# WarpCoreControl.net
KiCad netlist of a schematic drawn in EAGLE
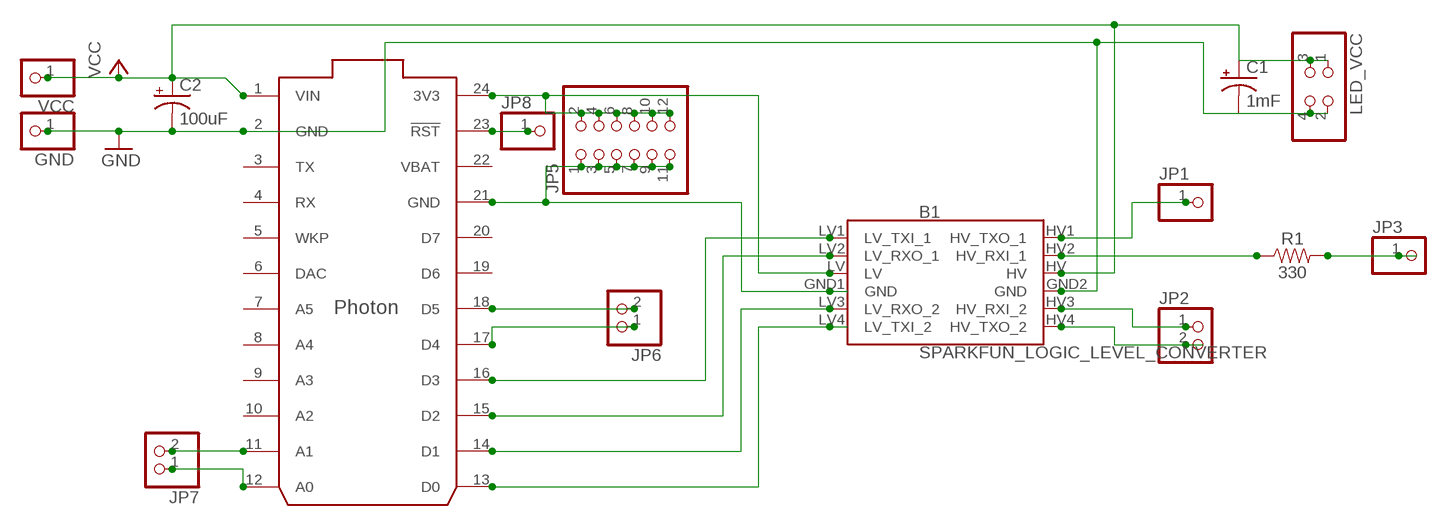
[diagram p0: schematic, sheet 1]

(export (version "E")
  (design (tool "Eeschema 10.0.6"))
  (components
    (comp (ref "B1")
      (value "SPARKFUN_LOGIC_LEVEL_CONVERTER")
      (footprint "eagle-import:SPARKFUN_LOGIC_LEVEL_CONVERTER")
      (libsource (lib "eagle-import") (part "SPARKFUN_LOGIC_LEVEL_CONVERTER"))
    )
    (comp (ref "C1")
      (value "1mF")
      (footprint "eagle-import:CPOL-RADIAL-5MM-10MM")
      (libsource (lib "eagle-import") (part "1000UF-RADIAL-5MM-25V-20%"))
    )
    (comp (ref "C2")
      (value "100uF")
      (footprint "eagle-import:CPOL-RADIAL-2.5MM-6.5MM")
      (libsource (lib "eagle-import") (part "100UF-POLAR-RADIAL-2.5MM-25V-20%"))
    )
    (comp (ref "GND")
      (value "PINHD-1X1")
      (footprint "eagle-import:1X01")
      (libsource (lib "eagle-import") (part "PINHD-1X1"))
    )
    (comp (ref "JP1")
      (value "PINHD-1X1")
      (footprint "eagle-import:1X01")
      (libsource (lib "eagle-import") (part "PINHD-1X1"))
    )
    (comp (ref "JP2")
      (value "PINHD-1X2")
      (footprint "eagle-import:1X02")
      (libsource (lib "eagle-import") (part "PINHD-1X2"))
    )
    (comp (ref "JP3")
      (value "PINHD-1X1")
      (footprint "eagle-import:1X01")
      (libsource (lib "eagle-import") (part "PINHD-1X1"))
    )
    (comp (ref "JP5")
      (value "PINHD-2X6")
      (footprint "eagle-import:2X06")
      (libsource (lib "eagle-import") (part "PINHD-2X6"))
    )
    (comp (ref "JP6")
      (value "PINHD-1X2")
      (footprint "eagle-import:1X02")
      (libsource (lib "eagle-import") (part "PINHD-1X2"))
    )
    (comp (ref "JP7")
      (value "PINHD-1X2")
      (footprint "eagle-import:1X02")
      (libsource (lib "eagle-import") (part "PINHD-1X2"))
    )
    (comp (ref "JP8")
      (value "PINHD-1X1")
      (footprint "eagle-import:1X01")
      (libsource (lib "eagle-import") (part "PINHD-1X1"))
    )
    (comp (ref "LED_VCC")
      (value "PINHD-2X2")
      (footprint "eagle-import:2X02")
      (libsource (lib "eagle-import") (part "PINHD-2X2"))
    )
    (comp (ref "R1")
      (value "330")
      (footprint "eagle-import:AXIAL-0.3")
      (libsource (lib "eagle-import") (part "RESISTORAXIAL-0.3"))
    )
    (comp (ref "U$1")
      (value "PHOTON_WITH_HEADERS")
      (footprint "eagle-import:PHOTON")
      (libsource (lib "eagle-import") (part "PHOTON_WITH_HEADERS"))
    )
    (comp (ref "VCC")
      (value "PINHD-1X1")
      (footprint "eagle-import:1X01")
      (libsource (lib "eagle-import") (part "PINHD-1X1"))
    )
  )
  (nets
    (net (code "1") (name "/VBAT") (class "Default")
      (node (ref "U$1") (pin "22") (pinfunction "VBAT_22") (pintype "power_in"))
    )
    (net (code "2") (name "GND") (class "Default")
      (node (ref "B1") (pin "GND1") (pinfunction "GND_GND1") (pintype "power_in"))
      (node (ref "B1") (pin "GND2") (pinfunction "GND_GND2") (pintype "power_in"))
      (node (ref "C1") (pin "-") (pinfunction "-_-") (pintype "passive"))
      (node (ref "C2") (pin "2") (pinfunction "-_2") (pintype "passive"))
      (node (ref "GND") (pin "1") (pinfunction "1_1") (pintype "passive"))
      (node (ref "JP5") (pin "1") (pinfunction "1_1") (pintype "passive"))
      (node (ref "JP5") (pin "11") (pinfunction "11_11") (pintype "passive"))
      (node (ref "JP5") (pin "3") (pinfunction "3_3") (pintype "passive"))
      (node (ref "JP5") (pin "5") (pinfunction "5_5") (pintype "passive"))
      (node (ref "JP5") (pin "7") (pinfunction "7_7") (pintype "passive"))
      (node (ref "JP5") (pin "9") (pinfunction "9_9") (pintype "passive"))
      (node (ref "LED_VCC") (pin "2") (pinfunction "2_2") (pintype "passive"))
      (node (ref "LED_VCC") (pin "4") (pinfunction "4_4") (pintype "passive"))
      (node (ref "U$1") (pin "2") (pinfunction "GND_2") (pintype "power_in"))
      (node (ref "U$1") (pin "21") (pinfunction "GND_21") (pintype "power_in"))
    )
    (net (code "3") (name "Net-(B1-HV_RXI_1)") (class "Default")
      (node (ref "B1") (pin "HV2") (pinfunction "HV_RXI_1_HV2") (pintype "bidirectional"))
      (node (ref "R1") (pin "P$1") (pinfunction "1_P$1") (pintype "passive"))
    )
    (net (code "4") (name "Net-(B1-HV_RXI_2)") (class "Default")
      (node (ref "B1") (pin "HV3") (pinfunction "HV_RXI_2_HV3") (pintype "bidirectional"))
      (node (ref "JP2") (pin "1") (pinfunction "1_1") (pintype "passive"))
    )
    (net (code "5") (name "Net-(B1-HV_TXO_1)") (class "Default")
      (node (ref "B1") (pin "HV1") (pinfunction "HV_TXO_1_HV1") (pintype "bidirectional"))
      (node (ref "JP1") (pin "1") (pinfunction "1_1") (pintype "passive"))
    )
    (net (code "6") (name "Net-(B1-HV_TXO_2)") (class "Default")
      (node (ref "B1") (pin "HV4") (pinfunction "HV_TXO_2_HV4") (pintype "bidirectional"))
      (node (ref "JP2") (pin "2") (pinfunction "2_2") (pintype "passive"))
    )
    (net (code "7") (name "Net-(B1-LV_RXO_1)") (class "Default")
      (node (ref "B1") (pin "LV2") (pinfunction "LV_RXO_1_LV2") (pintype "bidirectional"))
      (node (ref "U$1") (pin "15") (pinfunction "D2_15") (pintype "bidirectional"))
    )
    (net (code "8") (name "Net-(B1-LV_RXO_2)") (class "Default")
      (node (ref "B1") (pin "LV3") (pinfunction "LV_RXO_2_LV3") (pintype "bidirectional"))
      (node (ref "U$1") (pin "14") (pinfunction "D1_14") (pintype "bidirectional"))
    )
    (net (code "9") (name "Net-(B1-LV_TXI_1)") (class "Default")
      (node (ref "B1") (pin "LV1") (pinfunction "LV_TXI_1_LV1") (pintype "bidirectional"))
      (node (ref "U$1") (pin "16") (pinfunction "D3_16") (pintype "bidirectional"))
    )
    (net (code "10") (name "Net-(B1-LV_TXI_2)") (class "Default")
      (node (ref "B1") (pin "LV4") (pinfunction "LV_TXI_2_LV4") (pintype "bidirectional"))
      (node (ref "U$1") (pin "13") (pinfunction "D0_13") (pintype "bidirectional"))
    )
    (net (code "11") (name "Net-(R1-2)") (class "Default")
      (node (ref "JP3") (pin "1") (pinfunction "1_1") (pintype "passive"))
      (node (ref "R1") (pin "P$2") (pinfunction "2_P$2") (pintype "passive"))
    )
    (net (code "12") (name "Net-(U$1-3V3)") (class "Default")
      (node (ref "B1") (pin "LV") (pinfunction "LV_LV") (pintype "power_in"))
      (node (ref "JP5") (pin "10") (pinfunction "10_10") (pintype "passive"))
      (node (ref "JP5") (pin "12") (pinfunction "12_12") (pintype "passive"))
      (node (ref "JP5") (pin "2") (pinfunction "2_2") (pintype "passive"))
      (node (ref "JP5") (pin "4") (pinfunction "4_4") (pintype "passive"))
      (node (ref "JP5") (pin "6") (pinfunction "6_6") (pintype "passive"))
      (node (ref "JP5") (pin "8") (pinfunction "8_8") (pintype "passive"))
      (node (ref "U$1") (pin "24") (pinfunction "3V3_24") (pintype "power_in"))
    )
    (net (code "13") (name "Net-(U$1-A0)") (class "Default")
      (node (ref "JP7") (pin "1") (pinfunction "1_1") (pintype "passive"))
      (node (ref "U$1") (pin "12") (pinfunction "A0_12") (pintype "bidirectional"))
    )
    (net (code "14") (name "Net-(U$1-A1)") (class "Default")
      (node (ref "JP7") (pin "2") (pinfunction "2_2") (pintype "passive"))
      (node (ref "U$1") (pin "11") (pinfunction "A1_11") (pintype "bidirectional"))
    )
    (net (code "15") (name "Net-(U$1-D4)") (class "Default")
      (node (ref "JP6") (pin "1") (pinfunction "1_1") (pintype "passive"))
      (node (ref "U$1") (pin "17") (pinfunction "D4_17") (pintype "bidirectional"))
    )
    (net (code "16") (name "Net-(U$1-D5)") (class "Default")
      (node (ref "JP6") (pin "2") (pinfunction "2_2") (pintype "passive"))
      (node (ref "U$1") (pin "18") (pinfunction "D5_18") (pintype "bidirectional"))
    )
    (net (code "17") (name "Net-(U$1-~{RST})") (class "Default")
      (node (ref "JP8") (pin "1") (pinfunction "1_1") (pintype "passive"))
      (node (ref "U$1") (pin "23") (pinfunction "~{RST}_23") (pintype "bidirectional"))
    )
    (net (code "18") (name "VCC") (class "Default")
      (node (ref "B1") (pin "HV") (pinfunction "HV_HV") (pintype "power_in"))
      (node (ref "C1") (pin "+") (pinfunction "+_+") (pintype "passive"))
      (node (ref "C2") (pin "1") (pinfunction "+_1") (pintype "passive"))
      (node (ref "LED_VCC") (pin "1") (pinfunction "1_1") (pintype "passive"))
      (node (ref "LED_VCC") (pin "3") (pinfunction "3_3") (pintype "passive"))
      (node (ref "U$1") (pin "1") (pinfunction "VIN_1") (pintype "power_in"))
      (node (ref "VCC") (pin "1") (pinfunction "1_1") (pintype "passive"))
    )
    (net (code "19") (name "unconnected-(U$1-A2-Pad10)") (class "Default")
      (node (ref "U$1") (pin "10") (pinfunction "A2_10") (pintype "bidirectional"))
    )
    (net (code "20") (name "unconnected-(U$1-A3-Pad9)") (class "Default")
      (node (ref "U$1") (pin "9") (pinfunction "A3_9") (pintype "bidirectional"))
    )
    (net (code "21") (name "unconnected-(U$1-A4-Pad8)") (class "Default")
      (node (ref "U$1") (pin "8") (pinfunction "A4_8") (pintype "bidirectional"))
    )
    (net (code "22") (name "unconnected-(U$1-A5-Pad7)") (class "Default")
      (node (ref "U$1") (pin "7") (pinfunction "A5_7") (pintype "bidirectional"))
    )
    (net (code "23") (name "unconnected-(U$1-D6-Pad19)") (class "Default")
      (node (ref "U$1") (pin "19") (pinfunction "D6_19") (pintype "bidirectional"))
    )
    (net (code "24") (name "unconnected-(U$1-D7-Pad20)") (class "Default")
      (node (ref "U$1") (pin "20") (pinfunction "D7_20") (pintype "bidirectional"))
    )
    (net (code "25") (name "unconnected-(U$1-DAC-Pad6)") (class "Default")
      (node (ref "U$1") (pin "6") (pinfunction "DAC_6") (pintype "bidirectional"))
    )
    (net (code "26") (name "unconnected-(U$1-RX-Pad4)") (class "Default")
      (node (ref "U$1") (pin "4") (pinfunction "RX_4") (pintype "bidirectional"))
    )
    (net (code "27") (name "unconnected-(U$1-TX-Pad3)") (class "Default")
      (node (ref "U$1") (pin "3") (pinfunction "TX_3") (pintype "bidirectional"))
    )
    (net (code "28") (name "unconnected-(U$1-WKP-Pad5)") (class "Default")
      (node (ref "U$1") (pin "5") (pinfunction "WKP_5") (pintype "bidirectional"))
    )
  )
)
